# CAN_IF.net
KiCad netlist of a schematic drawn in Altium Designer
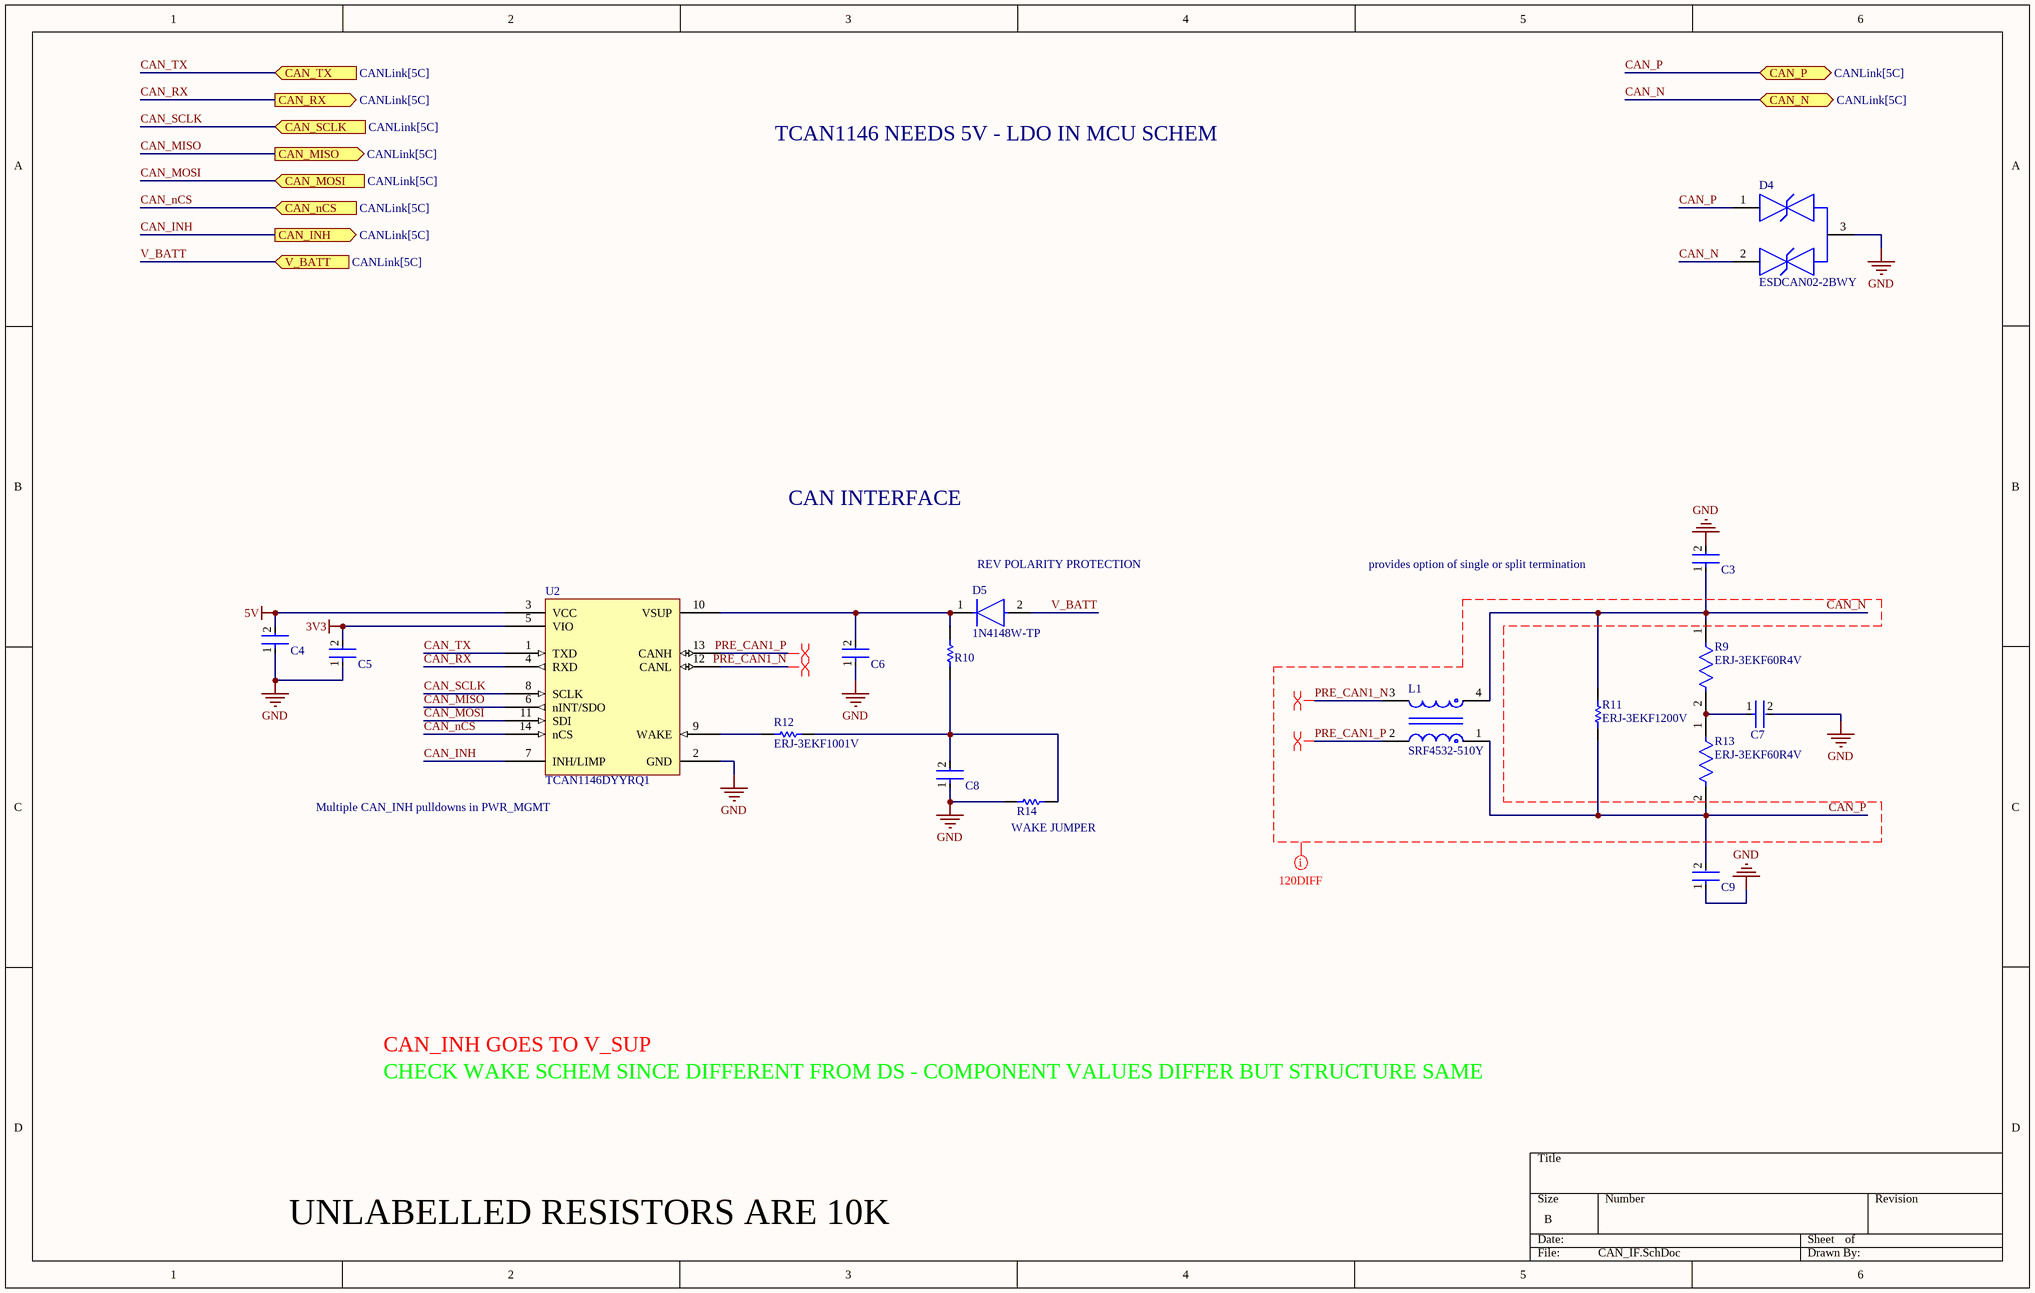
[diagram p0: CAN_IF.SchDoc]

(export (version "E")
  (design (tool "Eeschema 10.0.6"))
  (components
    (comp (ref "C3")
      (value "C0402C104K8PACTU")
      (footprint "FP-C0402-BB-MFG")
      (description "CAP CER 0.1UF 10V X5R 0402")
      (fields (field (name "MANUFACTURER") "Kemet") (field (name "TOLERANCE") "0.1"))
      (libsource (lib "Altium Content Vault") (part "b4654b650e69147ec39a6b967a45e02"))
    )
    (comp (ref "C4")
      (value "C0402C104K8PACTU")
      (footprint "FP-C0402-BB-MFG")
      (description "CAP CER 0.1UF 10V X5R 0402")
      (fields (field (name "MANUFACTURER") "Kemet") (field (name "TOLERANCE") "0.1"))
      (libsource (lib "Altium Content Vault") (part "b4654b650e69147ec39a6b967a45e02"))
    )
    (comp (ref "C5")
      (value "C0402C104K8PACTU")
      (footprint "FP-C0402-BB-MFG")
      (description "CAP CER 0.1UF 10V X5R 0402")
      (fields (field (name "MANUFACTURER") "Kemet") (field (name "TOLERANCE") "0.1"))
      (libsource (lib "Altium Content Vault") (part "b4654b650e69147ec39a6b967a45e02"))
    )
    (comp (ref "C6")
      (value "C0402C104K8PACTU")
      (footprint "FP-C0402-BB-MFG")
      (description "CAP CER 0.1UF 10V X5R 0402")
      (fields (field (name "MANUFACTURER") "Kemet") (field (name "TOLERANCE") "0.1"))
      (libsource (lib "Altium Content Vault") (part "b4654b650e69147ec39a6b967a45e02"))
    )
    (comp (ref "C7")
      (value "C0402C104K8PACTU")
      (footprint "FP-C0402-BB-MFG")
      (description "CAP CER 0.1UF 10V X5R 0402")
      (fields (field (name "MANUFACTURER") "Kemet") (field (name "TOLERANCE") "0.1"))
      (libsource (lib "Altium Content Vault") (part "b4654b650e69147ec39a6b967a45e02"))
    )
    (comp (ref "C8")
      (value "C0402C104K8PACTU")
      (footprint "FP-C0402-BB-MFG")
      (description "CAP CER 0.1UF 10V X5R 0402")
      (fields (field (name "MANUFACTURER") "Kemet") (field (name "TOLERANCE") "0.1"))
      (libsource (lib "Altium Content Vault") (part "b4654b650e69147ec39a6b967a45e02"))
    )
    (comp (ref "C9")
      (value "C0402C104K8PACTU")
      (footprint "FP-C0402-BB-MFG")
      (description "CAP CER 0.1UF 10V X5R 0402")
      (fields (field (name "MANUFACTURER") "Kemet") (field (name "TOLERANCE") "0.1"))
      (libsource (lib "Altium Content Vault") (part "b4654b650e69147ec39a6b967a45e02"))
    )
    (comp (ref "D4")
      (value "ESDCAN02-2BWY")
      (footprint "FP-SOT323-3L-MFG")
      (description "TVS DIODE 26.5V 44V SOT323-3")
      (fields
        (field (name "MANUFACTURER") "STMicroelectronics")
        (field (name "OCTOPART") "https://octopart.com/esdcan02-2bwy-stmicroelectronics-58631133")
      )
      (libsource (lib "Altium Content Vault") (part "0b9019fb5e52ed66df21ec1535be59d"))
    )
    (comp (ref "D5")
      (value "1N4148W-TP")
      (footprint "FP-SOD-123-IPC_A")
      (description "DIODE GEN PURP 100V 150MA SOD123")
      (libsource (lib "Altium Content Vault") (part "d7152d700b627762746794eb795d46e"))
    )
    (comp (ref "L1")
      (value "SRF4532-510Y")
      (footprint "FP-SRF4532-MFG")
      (description "CMC 51UH 200MA 2LN 2KOHM SMD")
      (fields (field (name "TOLERANCE") "50%"))
      (libsource (lib "Altium Content Vault") (part "aca3f6a10b859f211cca95010157f3b"))
    )
    (comp (ref "R9")
      (value "ERJ-3EKF60R4V")
      (footprint "FP-ERJ3EK-IPC_C")
      (description "RES SMD 60.4 OHM 1% 1/10W 0603")
      (fields (field (name "TOLERANCE") "1%"))
      (libsource (lib "Altium Content Vault") (part "1029c3af85768c4190bb7ad29bc67b5"))
    )
    (comp (ref "R10")
      (value "ERJ3EKF1002V")
      (footprint "RESC1609X55X30LL15T15")
      (description "Chip Resistor, 10 KOhm, +/- 1%, 0.1 W, -55 to 155 degC, 0603 (1608 Metric), RoHS, Tape and Reel")
      (fields (field (name "TOLERANCE") "1%") (field (name "MANUFACTURER") "Panasonic"))
      (libsource (lib "Altium Content Vault") (part "RES-2"))
    )
    (comp (ref "R11")
      (value "ERJ-3EKF1200V")
      (footprint "RESC1609X55X30ML15T15")
      (description "Chip Resistor, 120 Ohm, +/- 1%, 0.1 W, -55 to 155 degC, 0603 (1608 Metric), RoHS, Tape and Reel")
      (fields (field (name "TOLERANCE") "1%") (field (name "MANUFACTURER") "Panasonic"))
      (libsource (lib "Altium Content Vault") (part "RES-2"))
    )
    (comp (ref "R12")
      (value "ERJ-3EKF1001V")
      (footprint "RESC1608X55X30LL15T15")
      (fields (field (name "MANUFACTURER") "Panasonic"))
      (libsource (lib "Altium Content Vault") (part "RES"))
    )
    (comp (ref "R13")
      (value "ERJ-3EKF60R4V")
      (footprint "FP-ERJ3EK-IPC_C")
      (description "RES SMD 60.4 OHM 1% 1/10W 0603")
      (fields (field (name "TOLERANCE") "1%"))
      (libsource (lib "Altium Content Vault") (part "1029c3af85768c4190bb7ad29bc67b5"))
    )
    (comp (ref "R14")
      (value "0402 JUMPER 0 OHM")
      (footprint "RESC1005X40X25NL05T05")
      (description "READ THE NAME")
      (libsource (lib "uORocketry Hardware") (part "RES"))
    )
    (comp (ref "U2")
      (value "TCAN1146DYYRQ1")
      (footprint "TCAN1146DYYRQ1-Footprint-1")
      (libsource (lib "uORocketry Hardware") (part "TCAN1146DYYRQ1"))
    )
  )
  (nets
    (net (code "1") (name "/CAN_INH") (class "Default")
      (node (ref "U2") (pin "7") (pinfunction "INH/LIMP_7") (pintype "passive"))
    )
    (net (code "2") (name "/CAN_MISO") (class "Default")
      (node (ref "U2") (pin "6") (pinfunction "nINT/SDO_6") (pintype "output"))
    )
    (net (code "3") (name "/CAN_MOSI") (class "Default")
      (node (ref "U2") (pin "11") (pinfunction "SDI_11") (pintype "input"))
    )
    (net (code "4") (name "/CAN_N") (class "Default")
      (node (ref "C3") (pin "1") (pinfunction "1_1") (pintype "passive"))
      (node (ref "D4") (pin "2") (pinfunction "2_2") (pintype "passive"))
      (node (ref "L1") (pin "4") (pinfunction "4_4") (pintype "passive"))
      (node (ref "R11") (pin "1") (pinfunction "1_1") (pintype "passive"))
      (node (ref "R9") (pin "1") (pinfunction "1_1") (pintype "passive"))
    )
    (net (code "5") (name "/CAN_P") (class "Default")
      (node (ref "C9") (pin "2") (pinfunction "2_2") (pintype "passive"))
      (node (ref "D4") (pin "1") (pinfunction "1_1") (pintype "passive"))
      (node (ref "L1") (pin "1") (pinfunction "1_1") (pintype "passive"))
      (node (ref "R11") (pin "2") (pinfunction "2_2") (pintype "passive"))
      (node (ref "R13") (pin "2") (pinfunction "2_2") (pintype "passive"))
    )
    (net (code "6") (name "/CAN_RX") (class "Default")
      (node (ref "U2") (pin "4") (pinfunction "RXD_4") (pintype "output"))
    )
    (net (code "7") (name "/CAN_SCLK") (class "Default")
      (node (ref "U2") (pin "8") (pinfunction "SCLK_8") (pintype "input"))
    )
    (net (code "8") (name "/CAN_TX") (class "Default")
      (node (ref "U2") (pin "1") (pinfunction "TXD_1") (pintype "input"))
    )
    (net (code "9") (name "/CAN_nCS") (class "Default")
      (node (ref "U2") (pin "14") (pinfunction "nCS_14") (pintype "input"))
    )
    (net (code "10") (name "/PRE_CAN1_N") (class "Default")
      (node (ref "L1") (pin "3") (pinfunction "3_3") (pintype "passive"))
      (node (ref "U2") (pin "12") (pinfunction "CANL_12") (pintype "bidirectional"))
    )
    (net (code "11") (name "/PRE_CAN1_P") (class "Default")
      (node (ref "L1") (pin "2") (pinfunction "2_2") (pintype "passive"))
      (node (ref "U2") (pin "13") (pinfunction "CANH_13") (pintype "bidirectional"))
    )
    (net (code "12") (name "/V_BATT") (class "Default")
      (node (ref "D5") (pin "2") (pinfunction "A_2") (pintype "passive"))
    )
    (net (code "13") (name "3V3") (class "Default")
      (node (ref "C5") (pin "2") (pinfunction "2_2") (pintype "passive"))
      (node (ref "U2") (pin "5") (pinfunction "VIO_5") (pintype "power_in"))
    )
    (net (code "14") (name "5V") (class "Default")
      (node (ref "C4") (pin "2") (pinfunction "2_2") (pintype "passive"))
      (node (ref "U2") (pin "3") (pinfunction "VCC_3") (pintype "power_in"))
    )
    (net (code "15") (name "GND") (class "Default")
      (node (ref "C3") (pin "2") (pinfunction "2_2") (pintype "passive"))
      (node (ref "C4") (pin "1") (pinfunction "1_1") (pintype "passive"))
      (node (ref "C5") (pin "1") (pinfunction "1_1") (pintype "passive"))
      (node (ref "C6") (pin "1") (pinfunction "1_1") (pintype "passive"))
      (node (ref "C7") (pin "2") (pinfunction "2_2") (pintype "passive"))
      (node (ref "C8") (pin "1") (pinfunction "1_1") (pintype "passive"))
      (node (ref "C9") (pin "1") (pinfunction "1_1") (pintype "passive"))
      (node (ref "D4") (pin "3") (pinfunction "3_3") (pintype "passive"))
      (node (ref "R14") (pin "1") (pinfunction "1_1") (pintype "passive"))
      (node (ref "U2") (pin "2") (pinfunction "GND_2") (pintype "power_in"))
    )
    (net (code "16") (name "Net-(C7-Pad1)") (class "Default")
      (node (ref "C7") (pin "1") (pinfunction "1_1") (pintype "passive"))
      (node (ref "R13") (pin "1") (pinfunction "1_1") (pintype "passive"))
      (node (ref "R9") (pin "2") (pinfunction "2_2") (pintype "passive"))
    )
    (net (code "17") (name "Net-(C8-Pad2)") (class "Default")
      (node (ref "C8") (pin "2") (pinfunction "2_2") (pintype "passive"))
      (node (ref "R10") (pin "2") (pinfunction "2_2") (pintype "passive"))
      (node (ref "R12") (pin "2") (pinfunction "2_2") (pintype "passive"))
      (node (ref "R14") (pin "2") (pinfunction "2_2") (pintype "passive"))
    )
    (net (code "18") (name "Net-(D5-C)") (class "Default")
      (node (ref "C6") (pin "2") (pinfunction "2_2") (pintype "passive"))
      (node (ref "D5") (pin "1") (pinfunction "C_1") (pintype "passive"))
      (node (ref "R10") (pin "1") (pinfunction "1_1") (pintype "passive"))
      (node (ref "U2") (pin "10") (pinfunction "VSUP_10") (pintype "power_in"))
    )
    (net (code "19") (name "Net-(U2-WAKE)") (class "Default")
      (node (ref "R12") (pin "1") (pinfunction "1_1") (pintype "passive"))
      (node (ref "U2") (pin "9") (pinfunction "WAKE_9") (pintype "input"))
    )
  )
)
